# Sheet1.net
KiCad netlist of a schematic drawn in Altium Designer
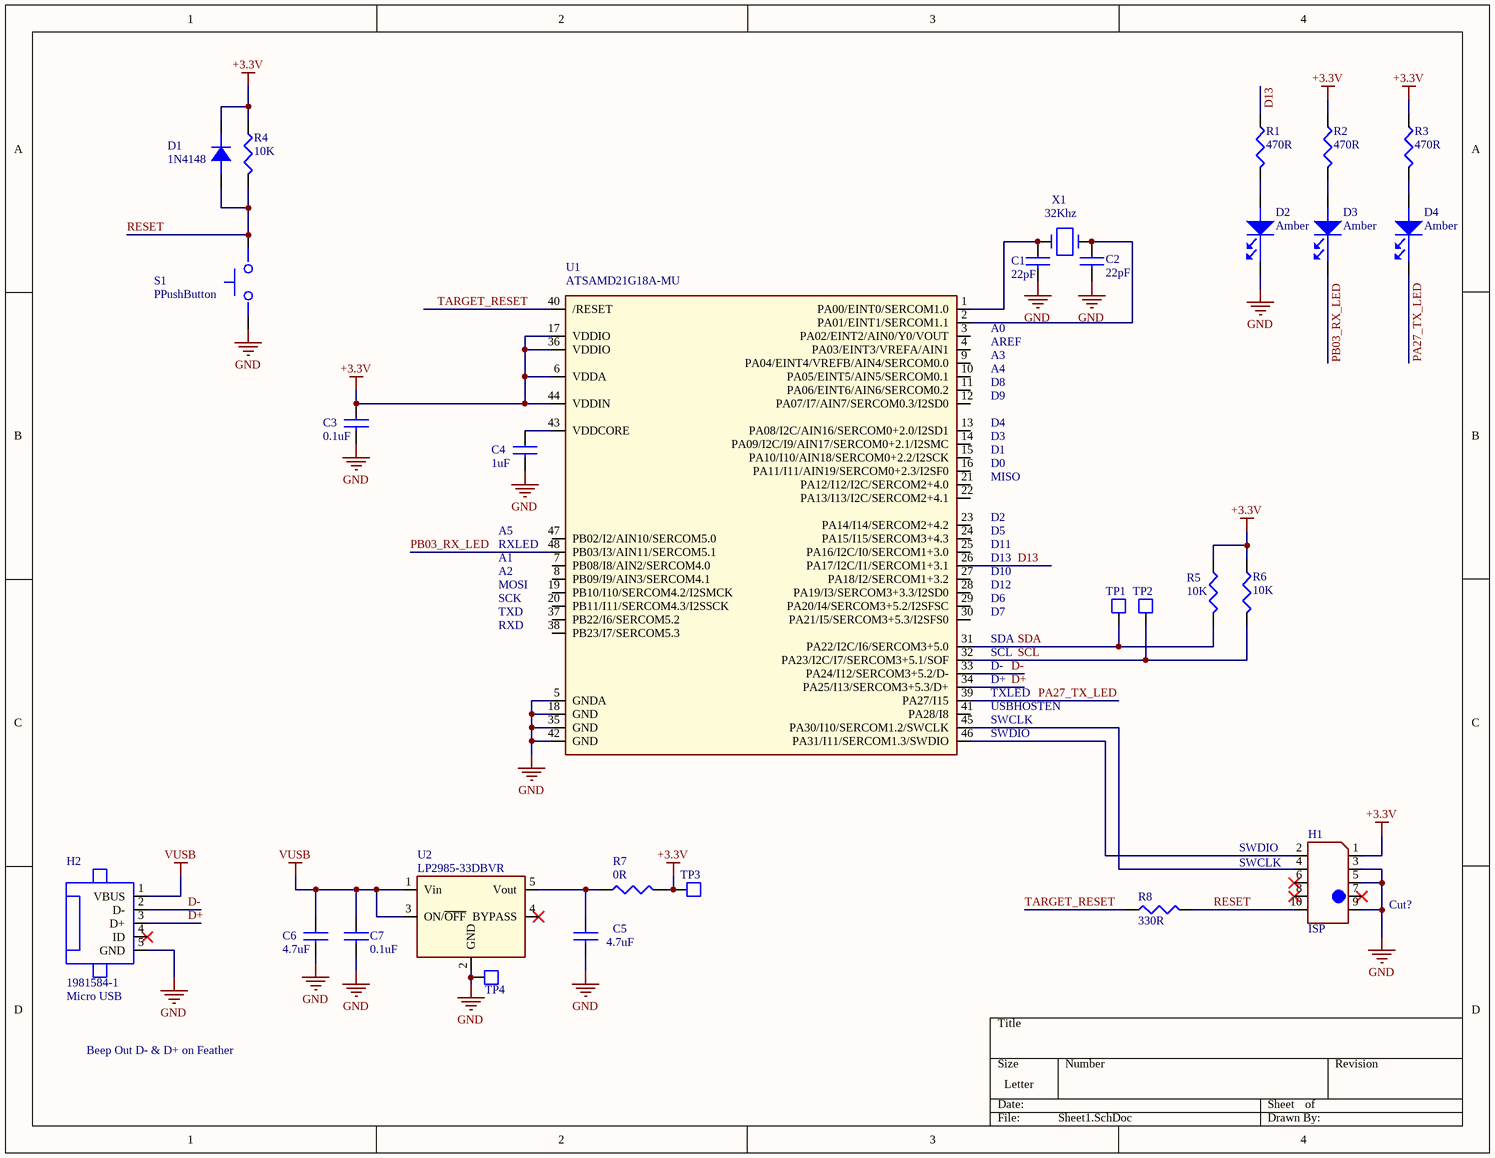
[diagram p0: Sheet1.SchDoc]

(export (version "E")
  (design (tool "Eeschema 10.0.6"))
  (components
    (comp (ref "C1")
      (value "22pF")
      (footprint "CAPC1005X56N")
      (description "CAP 0402")
      (libsource (lib "MAR") (part "CAP_0402"))
    )
    (comp (ref "C2")
      (value "22pF")
      (footprint "CAPC1005X56N")
      (description "CAP 0402")
      (libsource (lib "MAR") (part "CAP_0402"))
    )
    (comp (ref "C3")
      (value "0.1uF")
      (footprint "CAPC1005X56N")
      (description "CAP 0402")
      (libsource (lib "MAR") (part "CAP_0402"))
    )
    (comp (ref "C4")
      (value "1uF")
      (footprint "CAPC1005X56N")
      (description "CAP 0402")
      (libsource (lib "MAR") (part "CAP_0402"))
    )
    (comp (ref "C5")
      (value "4.7uF")
      (footprint "CAPC3216X160L")
      (description "CAP CER 4.7uF, 1206")
      (fields (field (name "Comment") "CAP_1206"))
      (libsource (lib "Parts_Library") (part "CAP_1206"))
    )
    (comp (ref "C6")
      (value "4.7uF")
      (footprint "CAPC3216X160L")
      (description "CAP CER 4.7uF, 1206")
      (fields (field (name "Comment") "CAP_1206"))
      (libsource (lib "Parts_Library") (part "CAP_1206"))
    )
    (comp (ref "C7")
      (value "0.1uF")
      (footprint "CAPC1608X09L")
      (description "CAP CER 0.1uF, 0603")
      (libsource (lib "Parts_Library") (part "CAP_0603"))
    )
    (comp (ref "D1")
      (value "1N4148")
      (footprint "SOD123")
      (description "DIODE SWITCH 100V 0.15A SOD123")
      (fields (field (name "MANUFACTURER") "Micro Commercial") (field (name "PARTNUMBER") "1N4148W-TP"))
      (libsource (lib "MAR") (part "1N4148W-TP"))
    )
    (comp (ref "D2")
      (value "LED_0603")
      (footprint "LED1608X55N-YELLOW")
      (fields (field (name "PARTNUMBER") "Amber"))
      (libsource (lib "MAR") (part "LED_0603"))
    )
    (comp (ref "D3")
      (value "LED_0603")
      (footprint "LED1608X55N-YELLOW")
      (fields (field (name "PARTNUMBER") "Amber"))
      (libsource (lib "MAR") (part "LED_0603"))
    )
    (comp (ref "D4")
      (value "LED_0603")
      (footprint "LED1608X55N-YELLOW")
      (fields (field (name "PARTNUMBER") "Amber"))
      (libsource (lib "MAR") (part "LED_0603"))
    )
    (comp (ref "H1")
      (value "ISP")
      (footprint "HDR5X2-50MIL")
      (description "JTAG CONN HEADER 5X2POS 50mil\" PADS")
      (fields (field (name "PARTNUMBER") "PADS"))
      (libsource (lib "MAR") (part "CON5X2"))
    )
    (comp (ref "H2")
      (value "Micro USB")
      (footprint "1981584-1")
      (description "CONN RCPT MICRO USB TYPE AB")
      (fields (field (name "MANUFACTURER") "TE Connectivity") (field (name "PARTNUMBER") "1981584-1"))
      (libsource (lib "MAR") (part "1981584-1"))
    )
    (comp (ref "R1")
      (value "470R")
      (footprint "RESC1005X40N")
      (description "RES 0402")
      (libsource (lib "MAR") (part "RES_0402"))
    )
    (comp (ref "R2")
      (value "470R")
      (footprint "RESC1005X40N")
      (description "RES 0402")
      (libsource (lib "MAR") (part "RES_0402"))
    )
    (comp (ref "R3")
      (value "470R")
      (footprint "RESC1005X40N")
      (description "RES 0402")
      (libsource (lib "MAR") (part "RES_0402"))
    )
    (comp (ref "R4")
      (value "10K")
      (footprint "RESC1005X40N")
      (description "RES 0402")
      (libsource (lib "MAR") (part "RES_0402"))
    )
    (comp (ref "R5")
      (value "10K")
      (footprint "RESC1005X40N")
      (description "RES 0402")
      (libsource (lib "MAR") (part "RES_0402"))
    )
    (comp (ref "R6")
      (value "10K")
      (footprint "RESC1005X40N")
      (description "RES 0402")
      (libsource (lib "MAR") (part "RES_0402"))
    )
    (comp (ref "R7")
      (value "0R")
      (footprint "RESC1005X40N")
      (description "RES 0402")
      (libsource (lib "MAR") (part "RES_0402"))
    )
    (comp (ref "R8")
      (value "330R")
      (footprint "RESC1005X40N")
      (description "RES 0402")
      (libsource (lib "MAR") (part "RES_0402"))
    )
    (comp (ref "S1")
      (value "PPushButton")
      (footprint "TL1015AF160QG")
      (description "DX_SWITCH TACTILE")
      (fields (field (name "PARTNUMBER") "122514"))
      (libsource (lib "MAR") (part "DX_MINI_TACT_SWITCH"))
    )
    (comp (ref "TP1")
      (value "Test Point, 1mm Top Layer")
      (footprint "TP100TL")
      (libsource (lib "") (part "Test Point, 1mm Top Layer_1"))
    )
    (comp (ref "TP2")
      (value "Test Point, 1mm Top Layer")
      (footprint "TP100TL")
      (libsource (lib "") (part "Test Point, 1mm Top Layer_1"))
    )
    (comp (ref "TP3")
      (value "Test Point, 1mm Top Layer")
      (footprint "TP100TL")
      (libsource (lib "MAR") (part "Test Point, 1mm Top Layer"))
    )
    (comp (ref "TP4")
      (value "Test Point, 1mm Top Layer")
      (footprint "TP100TL")
      (libsource (lib "MAR") (part "Test Point, 1mm Top Layer"))
    )
    (comp (ref "U1")
      (value "ATSAMD21G18A-MU")
      (footprint "LQFP48")
      (description "IC MCU 32BIT 256KB FLASH 48QFN")
      (fields (field (name "MANUFACTURER") "Atmel") (field (name "PARTNUMBER") "ATSAMD21G18A-MU"))
      (libsource (lib "MAR") (part "ATSAMD21G18A-MU"))
    )
    (comp (ref "U2")
      (value "LP2985-33DBVR")
      (footprint "SOT95P280X144-5N")
      (description "IC REG LDO 3.3V .15A SOT23-5")
      (fields (field (name "MANUFACTURER") "Texas Instruments") (field (name "PARTNUMBER") "LP2985-33DBVR"))
      (libsource (lib "MAR") (part "LP2985-33DBVR"))
    )
    (comp (ref "X1")
      (value "32Khz")
      (footprint "ECS-.327-12.5-34B")
      (description "CRYSTAL 32.768 KHZ 12.5PF SMD")
      (fields (field (name "PARTNUMBER") "ECS-.327-12.5-34B") (field (name "MANUFACTURER") "ECS"))
      (libsource (lib "MAR") (part "ECS-.327-12.5-34B"))
    )
  )
  (nets
    (net (code "1") (name "+3.3V") (class "Default")
      (node (ref "C3") (pin "1") (pinfunction "1_1") (pintype "passive"))
      (node (ref "D1") (pin "1") (pinfunction "Cathode_1") (pintype "passive"))
      (node (ref "H1") (pin "1") (pintype "passive"))
      (node (ref "R2") (pin "1") (pinfunction "1_1") (pintype "passive"))
      (node (ref "R3") (pin "1") (pinfunction "1_1") (pintype "passive"))
      (node (ref "R4") (pin "1") (pinfunction "1_1") (pintype "passive"))
      (node (ref "R5") (pin "1") (pinfunction "1_1") (pintype "passive"))
      (node (ref "R6") (pin "1") (pinfunction "1_1") (pintype "passive"))
      (node (ref "R7") (pin "2") (pinfunction "2_2") (pintype "passive"))
      (node (ref "TP3") (pin "1") (pinfunction "1_1") (pintype "passive"))
      (node (ref "U1") (pin "17") (pinfunction "VDDIO_17") (pintype "power_in"))
      (node (ref "U1") (pin "36") (pinfunction "VDDIO_36") (pintype "power_in"))
      (node (ref "U1") (pin "44") (pinfunction "VDDIN_44") (pintype "power_in"))
      (node (ref "U1") (pin "6") (pinfunction "VDDA_6") (pintype "power_in"))
    )
    (net (code "2") (name "/D+") (class "Default")
      (node (ref "H2") (pin "3") (pinfunction "D+_3") (pintype "passive"))
      (node (ref "U1") (pin "34") (pinfunction "PA25/I13/SERCOM3+5.3/D+_34") (pintype "passive"))
    )
    (net (code "3") (name "/D-") (class "Default")
      (node (ref "H2") (pin "2") (pinfunction "D-_2") (pintype "passive"))
      (node (ref "U1") (pin "33") (pinfunction "PA24/I12/SERCOM3+5.2/D-_33") (pintype "passive"))
    )
    (net (code "4") (name "/D13") (class "Default")
      (node (ref "R1") (pin "1") (pinfunction "1_1") (pintype "passive"))
      (node (ref "U1") (pin "26") (pinfunction "PA17/I2C/I1/SERCOM1+3.1_26") (pintype "passive"))
    )
    (net (code "5") (name "/PA27_TX_LED") (class "Default")
      (node (ref "D4") (pin "1") (pinfunction "CATHODE_1") (pintype "passive"))
      (node (ref "U1") (pin "39") (pinfunction "PA27/I15_39") (pintype "passive"))
    )
    (net (code "6") (name "/PB03_RX_LED") (class "Default")
      (node (ref "D3") (pin "1") (pinfunction "CATHODE_1") (pintype "passive"))
      (node (ref "U1") (pin "48") (pinfunction "PB03/I3/AIN11/SERCOM5.1_48") (pintype "passive"))
    )
    (net (code "7") (name "/RESET") (class "Default")
      (node (ref "D1") (pin "2") (pinfunction "Annode_2") (pintype "passive"))
      (node (ref "H1") (pin "10") (pintype "passive"))
      (node (ref "R4") (pin "2") (pinfunction "2_2") (pintype "passive"))
      (node (ref "R8") (pin "2") (pinfunction "2_2") (pintype "passive"))
      (node (ref "S1") (pin "2") (pinfunction "B_2") (pintype "passive"))
    )
    (net (code "8") (name "/SCL") (class "Default")
      (node (ref "R6") (pin "2") (pinfunction "2_2") (pintype "passive"))
      (node (ref "TP2") (pin "1") (pinfunction "1_1") (pintype "passive"))
      (node (ref "U1") (pin "32") (pinfunction "PA23/I2C/I7/SERCOM3+5.1/SOF_32") (pintype "passive"))
    )
    (net (code "9") (name "/SDA") (class "Default")
      (node (ref "R5") (pin "2") (pinfunction "2_2") (pintype "passive"))
      (node (ref "TP1") (pin "1") (pinfunction "1_1") (pintype "passive"))
      (node (ref "U1") (pin "31") (pinfunction "PA22/I2C/I6/SERCOM3+5.0_31") (pintype "passive"))
    )
    (net (code "10") (name "/TARGET_RESET") (class "Default")
      (node (ref "R8") (pin "1") (pinfunction "1_1") (pintype "passive"))
      (node (ref "U1") (pin "40") (pinfunction "/RESET_40") (pintype "passive"))
    )
    (net (code "11") (name "GND") (class "Default")
      (node (ref "C1") (pin "2") (pinfunction "2_2") (pintype "passive"))
      (node (ref "C2") (pin "2") (pinfunction "2_2") (pintype "passive"))
      (node (ref "C3") (pin "2") (pinfunction "2_2") (pintype "passive"))
      (node (ref "C4") (pin "2") (pinfunction "2_2") (pintype "passive"))
      (node (ref "C5") (pin "2") (pinfunction "2_2") (pintype "passive"))
      (node (ref "C6") (pin "2") (pinfunction "2_2") (pintype "passive"))
      (node (ref "C7") (pin "2") (pinfunction "2_2") (pintype "passive"))
      (node (ref "D2") (pin "1") (pinfunction "CATHODE_1") (pintype "passive"))
      (node (ref "H1") (pin "3") (pintype "passive"))
      (node (ref "H1") (pin "5") (pintype "passive"))
      (node (ref "H1") (pin "9") (pintype "passive"))
      (node (ref "H2") (pin "5") (pinfunction "GND_5") (pintype "power_in"))
      (node (ref "S1") (pin "1") (pinfunction "A_1") (pintype "passive"))
      (node (ref "TP4") (pin "1") (pinfunction "1_1") (pintype "passive"))
      (node (ref "U1") (pin "18") (pinfunction "GND_18") (pintype "power_in"))
      (node (ref "U1") (pin "35") (pinfunction "GND_35") (pintype "power_in"))
      (node (ref "U1") (pin "42") (pinfunction "GND_42") (pintype "power_in"))
      (node (ref "U1") (pin "5") (pinfunction "GNDA_5") (pintype "power_in"))
      (node (ref "U2") (pin "2") (pinfunction "GND_2") (pintype "power_in"))
    )
    (net (code "12") (name "Net-(D2-ANODE)") (class "Default")
      (node (ref "D2") (pin "2") (pinfunction "ANODE_2") (pintype "passive"))
      (node (ref "R1") (pin "2") (pinfunction "2_2") (pintype "passive"))
    )
    (net (code "13") (name "Net-(D3-ANODE)") (class "Default")
      (node (ref "D3") (pin "2") (pinfunction "ANODE_2") (pintype "passive"))
      (node (ref "R2") (pin "2") (pinfunction "2_2") (pintype "passive"))
    )
    (net (code "14") (name "Net-(D4-ANODE)") (class "Default")
      (node (ref "D4") (pin "2") (pinfunction "ANODE_2") (pintype "passive"))
      (node (ref "R3") (pin "2") (pinfunction "2_2") (pintype "passive"))
    )
    (net (code "15") (name "Net-(U1-PA00{slash}EINT0{slash}SERCOM1.0)") (class "Default")
      (node (ref "C1") (pin "1") (pinfunction "1_1") (pintype "passive"))
      (node (ref "U1") (pin "1") (pinfunction "PA00/EINT0/SERCOM1.0_1") (pintype "passive"))
      (node (ref "X1") (pin "1") (pinfunction "1_1") (pintype "passive"))
    )
    (net (code "16") (name "Net-(U1-PA01{slash}EINT1{slash}SERCOM1.1)") (class "Default")
      (node (ref "C2") (pin "1") (pinfunction "1_1") (pintype "passive"))
      (node (ref "U1") (pin "2") (pinfunction "PA01/EINT1/SERCOM1.1_2") (pintype "passive"))
      (node (ref "X1") (pin "2") (pinfunction "2_2") (pintype "passive"))
    )
    (net (code "17") (name "Net-(U1-PA30{slash}I10{slash}SERCOM1.2{slash}SWCLK)") (class "Default")
      (node (ref "H1") (pin "4") (pintype "passive"))
      (node (ref "U1") (pin "45") (pinfunction "PA30/I10/SERCOM1.2/SWCLK_45") (pintype "passive"))
    )
    (net (code "18") (name "Net-(U1-PA31{slash}I11{slash}SERCOM1.3{slash}SWDIO)") (class "Default")
      (node (ref "H1") (pin "2") (pintype "passive"))
      (node (ref "U1") (pin "46") (pinfunction "PA31/I11/SERCOM1.3/SWDIO_46") (pintype "passive"))
    )
    (net (code "19") (name "Net-(U1-VDDCORE)") (class "Default")
      (node (ref "C4") (pin "1") (pinfunction "1_1") (pintype "passive"))
      (node (ref "U1") (pin "43") (pinfunction "VDDCORE_43") (pintype "power_in"))
    )
    (net (code "20") (name "Net-(U2-Vout)") (class "Default")
      (node (ref "C5") (pin "1") (pinfunction "1_1") (pintype "passive"))
      (node (ref "R7") (pin "1") (pinfunction "1_1") (pintype "passive"))
      (node (ref "U2") (pin "5") (pinfunction "Vout_5") (pintype "passive"))
    )
    (net (code "21") (name "VUSB") (class "Default")
      (node (ref "C6") (pin "1") (pinfunction "1_1") (pintype "passive"))
      (node (ref "C7") (pin "1") (pinfunction "1_1") (pintype "passive"))
      (node (ref "H2") (pin "1") (pinfunction "VBUS_1") (pintype "power_in"))
      (node (ref "U2") (pin "1") (pinfunction "Vin_1") (pintype "passive"))
      (node (ref "U2") (pin "3") (pinfunction "ON/~{OFF}_3") (pintype "passive"))
    )
    (net (code "22") (name "unconnected-(H1-Pad6)") (class "Default")
      (node (ref "H1") (pin "6") (pintype "passive+no_connect"))
    )
    (net (code "23") (name "unconnected-(H1-Pad7)") (class "Default")
      (node (ref "H1") (pin "7") (pintype "passive+no_connect"))
    )
    (net (code "24") (name "unconnected-(H1-Pad8)") (class "Default")
      (node (ref "H1") (pin "8") (pintype "passive+no_connect"))
    )
    (net (code "25") (name "unconnected-(H2-ID-Pad4)") (class "Default")
      (node (ref "H2") (pin "4") (pinfunction "ID_4") (pintype "passive+no_connect"))
    )
    (net (code "26") (name "unconnected-(U1-PA02{slash}EINT2{slash}AIN0{slash}Y0{slash}VOUT-Pad3)") (class "Default")
      (node (ref "U1") (pin "3") (pinfunction "PA02/EINT2/AIN0/Y0/VOUT_3") (pintype "passive"))
    )
    (net (code "27") (name "unconnected-(U1-PA03{slash}EINT3{slash}VREFA{slash}AIN1-Pad4)") (class "Default")
      (node (ref "U1") (pin "4") (pinfunction "PA03/EINT3/VREFA/AIN1_4") (pintype "passive"))
    )
    (net (code "28") (name "unconnected-(U1-PA04{slash}EINT4{slash}VREFB{slash}AIN4{slash}SERCOM0.0-Pad9)") (class "Default")
      (node (ref "U1") (pin "9") (pinfunction "PA04/EINT4/VREFB/AIN4/SERCOM0.0_9") (pintype "passive"))
    )
    (net (code "29") (name "unconnected-(U1-PA05{slash}EINT5{slash}AIN5{slash}SERCOM0.1-Pad10)") (class "Default")
      (node (ref "U1") (pin "10") (pinfunction "PA05/EINT5/AIN5/SERCOM0.1_10") (pintype "passive"))
    )
    (net (code "30") (name "unconnected-(U1-PA06{slash}EINT6{slash}AIN6{slash}SERCOM0.2-Pad11)") (class "Default")
      (node (ref "U1") (pin "11") (pinfunction "PA06/EINT6/AIN6/SERCOM0.2_11") (pintype "passive"))
    )
    (net (code "31") (name "unconnected-(U1-PA07{slash}I7{slash}AIN7{slash}SERCOM0.3{slash}I2SD0-Pad12)") (class "Default")
      (node (ref "U1") (pin "12") (pinfunction "PA07/I7/AIN7/SERCOM0.3/I2SD0_12") (pintype "passive"))
    )
    (net (code "32") (name "unconnected-(U1-PA08{slash}I2C{slash}AIN16{slash}SERCOM0+2.0{slash}I2SD1-Pad13)") (class "Default")
      (node (ref "U1") (pin "13") (pinfunction "PA08/I2C/AIN16/SERCOM0+2.0/I2SD1_13") (pintype "passive"))
    )
    (net (code "33") (name "unconnected-(U1-PA09{slash}I2C{slash}I9{slash}AIN17{slash}SERCOM0+2.1{slash}I2SMC-Pad14)") (class "Default")
      (node (ref "U1") (pin "14") (pinfunction "PA09/I2C/I9/AIN17/SERCOM0+2.1/I2SMC_14") (pintype "passive"))
    )
    (net (code "34") (name "unconnected-(U1-PA10{slash}I10{slash}AIN18{slash}SERCOM0+2.2{slash}I2SCK-Pad15)") (class "Default")
      (node (ref "U1") (pin "15") (pinfunction "PA10/I10/AIN18/SERCOM0+2.2/I2SCK_15") (pintype "passive"))
    )
    (net (code "35") (name "unconnected-(U1-PA11{slash}I11{slash}AIN19{slash}SERCOM0+2.3{slash}I2SF0-Pad16)") (class "Default")
      (node (ref "U1") (pin "16") (pinfunction "PA11/I11/AIN19/SERCOM0+2.3/I2SF0_16") (pintype "passive"))
    )
    (net (code "36") (name "unconnected-(U1-PA12{slash}I12{slash}I2C{slash}SERCOM2+4.0-Pad21)") (class "Default")
      (node (ref "U1") (pin "21") (pinfunction "PA12/I12/I2C/SERCOM2+4.0_21") (pintype "passive"))
    )
    (net (code "37") (name "unconnected-(U1-PA13{slash}I13{slash}I2C{slash}SERCOM2+4.1-Pad22)") (class "Default")
      (node (ref "U1") (pin "22") (pinfunction "PA13/I13/I2C/SERCOM2+4.1_22") (pintype "passive"))
    )
    (net (code "38") (name "unconnected-(U1-PA14{slash}I14{slash}SERCOM2+4.2-Pad23)") (class "Default")
      (node (ref "U1") (pin "23") (pinfunction "PA14/I14/SERCOM2+4.2_23") (pintype "passive"))
    )
    (net (code "39") (name "unconnected-(U1-PA15{slash}I15{slash}SERCOM3+4.3-Pad24)") (class "Default")
      (node (ref "U1") (pin "24") (pinfunction "PA15/I15/SERCOM3+4.3_24") (pintype "passive"))
    )
    (net (code "40") (name "unconnected-(U1-PA16{slash}I2C{slash}I0{slash}SERCOM1+3.0-Pad25)") (class "Default")
      (node (ref "U1") (pin "25") (pinfunction "PA16/I2C/I0/SERCOM1+3.0_25") (pintype "passive"))
    )
    (net (code "41") (name "unconnected-(U1-PA18{slash}I2{slash}SERCOM1+3.2-Pad27)") (class "Default")
      (node (ref "U1") (pin "27") (pinfunction "PA18/I2/SERCOM1+3.2_27") (pintype "passive"))
    )
    (net (code "42") (name "unconnected-(U1-PA19{slash}I3{slash}SERCOM3+3.3{slash}I2SD0-Pad28)") (class "Default")
      (node (ref "U1") (pin "28") (pinfunction "PA19/I3/SERCOM3+3.3/I2SD0_28") (pintype "passive"))
    )
    (net (code "43") (name "unconnected-(U1-PA20{slash}I4{slash}SERCOM3+5.2{slash}I2SFSC-Pad29)") (class "Default")
      (node (ref "U1") (pin "29") (pinfunction "PA20/I4/SERCOM3+5.2/I2SFSC_29") (pintype "passive"))
    )
    (net (code "44") (name "unconnected-(U1-PA21{slash}I5{slash}SERCOM3+5.3{slash}I2SFS0-Pad30)") (class "Default")
      (node (ref "U1") (pin "30") (pinfunction "PA21/I5/SERCOM3+5.3/I2SFS0_30") (pintype "passive"))
    )
    (net (code "45") (name "unconnected-(U1-PA28{slash}I8-Pad41)") (class "Default")
      (node (ref "U1") (pin "41") (pinfunction "PA28/I8_41") (pintype "passive"))
    )
    (net (code "46") (name "unconnected-(U1-PB02{slash}I2{slash}AIN10{slash}SERCOM5.0-Pad47)") (class "Default")
      (node (ref "U1") (pin "47") (pinfunction "PB02/I2/AIN10/SERCOM5.0_47") (pintype "passive"))
    )
    (net (code "47") (name "unconnected-(U1-PB08{slash}I8{slash}AIN2{slash}SERCOM4.0-Pad7)") (class "Default")
      (node (ref "U1") (pin "7") (pinfunction "PB08/I8/AIN2/SERCOM4.0_7") (pintype "passive"))
    )
    (net (code "48") (name "unconnected-(U1-PB09{slash}I9{slash}AIN3{slash}SERCOM4.1-Pad8)") (class "Default")
      (node (ref "U1") (pin "8") (pinfunction "PB09/I9/AIN3/SERCOM4.1_8") (pintype "passive"))
    )
    (net (code "49") (name "unconnected-(U1-PB10{slash}I10{slash}SERCOM4.2{slash}I2SMCK-Pad19)") (class "Default")
      (node (ref "U1") (pin "19") (pinfunction "PB10/I10/SERCOM4.2/I2SMCK_19") (pintype "passive"))
    )
    (net (code "50") (name "unconnected-(U1-PB11{slash}I11{slash}SERCOM4.3{slash}I2SSCK-Pad20)") (class "Default")
      (node (ref "U1") (pin "20") (pinfunction "PB11/I11/SERCOM4.3/I2SSCK_20") (pintype "passive"))
    )
    (net (code "51") (name "unconnected-(U1-PB22{slash}I6{slash}SERCOM5.2-Pad37)") (class "Default")
      (node (ref "U1") (pin "37") (pinfunction "PB22/I6/SERCOM5.2_37") (pintype "passive"))
    )
    (net (code "52") (name "unconnected-(U1-PB23{slash}I7{slash}SERCOM5.3-Pad38)") (class "Default")
      (node (ref "U1") (pin "38") (pinfunction "PB23/I7/SERCOM5.3_38") (pintype "passive"))
    )
    (net (code "53") (name "unconnected-(U2-BYPASS-Pad4)") (class "Default")
      (node (ref "U2") (pin "4") (pinfunction "BYPASS_4") (pintype "passive+no_connect"))
    )
  )
)
